# Power_Managment.net
KiCad netlist of a schematic drawn in Altium Designer
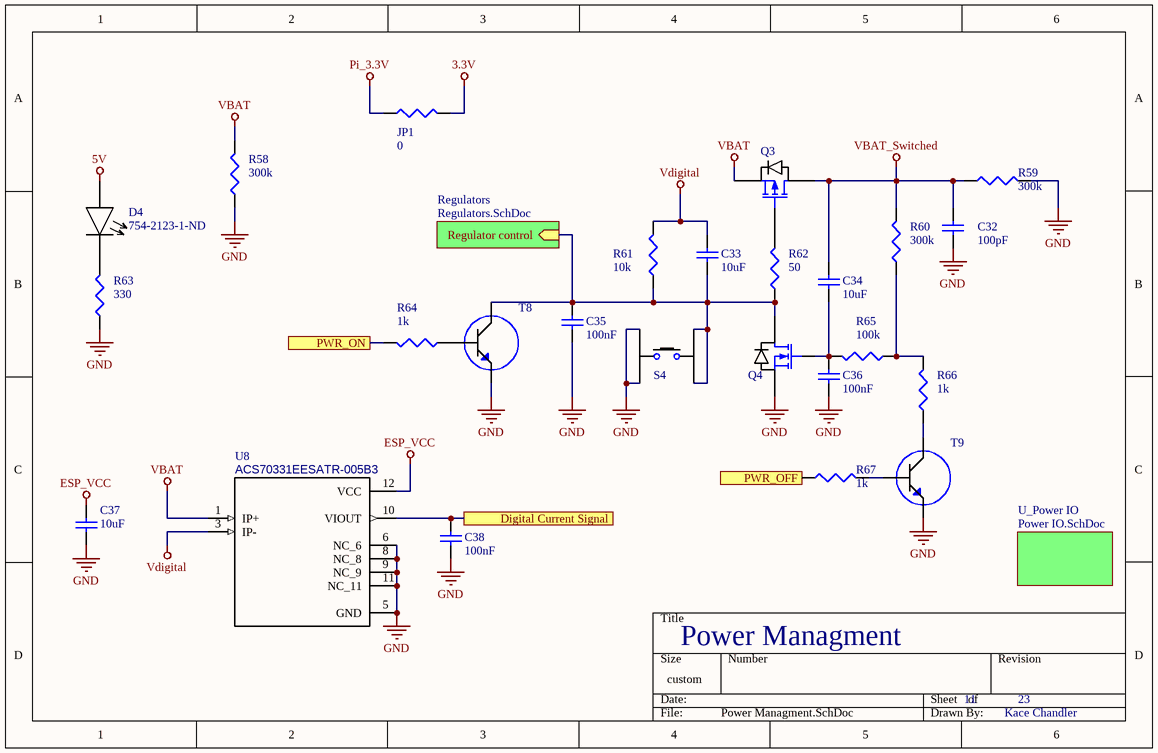
[diagram p0: Power Managment.SchDoc]

(export (version "E")
  (design (tool "Eeschema 10.0.6"))
  (components
    (comp (ref "C32")
      (value "100pF")
      (footprint "Electrolytic Cap")
      (description "Capacitor")
      (fields (field (name "Comment") "Cap") (field (name "PUBLISHER") "Altium Limited"))
      (libsource (lib "Miscellaneous Devices") (part "Cap"))
    )
    (comp (ref "C33")
      (value "10uF")
      (footprint "0603 to 0805 SMD")
      (description "Capacitor")
      (fields (field (name "Comment") "Cap") (field (name "PUBLISHER") "Altium Limited"))
      (libsource (lib "Miscellaneous Devices") (part "Cap"))
    )
    (comp (ref "C34")
      (value "10uF")
      (footprint "0603 to 0805 SMD")
      (description "Capacitor")
      (fields (field (name "Comment") "Cap") (field (name "PUBLISHER") "Altium Limited"))
      (libsource (lib "Miscellaneous Devices") (part "Cap"))
    )
    (comp (ref "C35")
      (value "100nF")
      (footprint "0603 to 0805 SMD")
      (description "Capacitor")
      (fields (field (name "Comment") "Cap") (field (name "PUBLISHER") "Altium Limited"))
      (libsource (lib "Miscellaneous Devices") (part "Cap"))
    )
    (comp (ref "C36")
      (value "100nF")
      (footprint "0603 to 0805 SMD")
      (description "Capacitor")
      (fields (field (name "Comment") "Cap") (field (name "PUBLISHER") "Altium Limited"))
      (libsource (lib "Miscellaneous Devices") (part "Cap"))
    )
    (comp (ref "C37")
      (value "10uF")
      (footprint "0805 Footprint")
      (description "Capacitor")
      (fields (field (name "Comment") "Cap") (field (name "PUBLISHER") "Altium Limited"))
      (libsource (lib "Miscellaneous Devices") (part "Cap"))
    )
    (comp (ref "C38")
      (value "100nF")
      (footprint "0805 Footprint")
      (description "Capacitor")
      (fields (field (name "Comment") "Cap") (field (name "PUBLISHER") "Altium Limited"))
      (libsource (lib "Miscellaneous Devices") (part "Cap"))
    )
    (comp (ref "D4")
      (value "LED_R")
      (footprint "0402 footprint")
      (fields (field (name "SUPPLIER PART NUMBER 1") "754-2123-1-ND"))
      (libsource (lib "AvionicsParts") (part "LED_R"))
    )
    (comp (ref "JP1")
      (value "0")
      (footprint "0603 TO 1210 SMD")
      (description "Resistor")
      (fields (field (name "Comment") "Res3") (field (name "PUBLISHER") "Altium Limited"))
      (libsource (lib "Miscellaneous Devices") (part "Res3"))
    )
    (comp (ref "Q3")
      (value "P-Channel")
      (footprint "P Channel MOSFET")
      (libsource (lib "AvionicsParts") (part "P-Channel"))
    )
    (comp (ref "Q4")
      (value "N-Channel")
      (footprint "N Channel MOSFET")
      (libsource (lib "AvionicsParts") (part "N-Channel"))
    )
    (comp (ref "R58")
      (value "300k")
      (footprint "0603 Footprint")
      (description "Resistor")
      (fields (field (name "Comment") "Res3") (field (name "PUBLISHER") "Altium Limited"))
      (libsource (lib "Miscellaneous Devices") (part "Res3"))
    )
    (comp (ref "R59")
      (value "300k")
      (footprint "0603 Footprint")
      (description "Resistor")
      (fields (field (name "Comment") "Res3") (field (name "PUBLISHER") "Altium Limited"))
      (libsource (lib "Miscellaneous Devices") (part "Res3"))
    )
    (comp (ref "R60")
      (value "300k")
      (footprint "0603 Footprint")
      (description "Resistor")
      (fields (field (name "Comment") "Res3") (field (name "PUBLISHER") "Altium Limited"))
      (libsource (lib "Miscellaneous Devices") (part "Res3"))
    )
    (comp (ref "R61")
      (value "10k")
      (footprint "0603 Footprint")
      (description "Resistor")
      (fields (field (name "Comment") "Res3") (field (name "PUBLISHER") "Altium Limited"))
      (libsource (lib "Miscellaneous Devices") (part "Res3"))
    )
    (comp (ref "R62")
      (value "50")
      (footprint "0603 Footprint")
      (description "Resistor")
      (fields (field (name "Comment") "Res3") (field (name "PUBLISHER") "Altium Limited"))
      (libsource (lib "Miscellaneous Devices") (part "Res3"))
    )
    (comp (ref "R63")
      (value "330")
      (footprint "0603 Footprint")
      (description "Resistor")
      (fields (field (name "Comment") "Res3") (field (name "PUBLISHER") "Altium Limited"))
      (libsource (lib "Miscellaneous Devices") (part "Res3"))
    )
    (comp (ref "R64")
      (value "1k")
      (footprint "0603 Footprint")
      (description "Resistor")
      (fields (field (name "Comment") "Res3") (field (name "PUBLISHER") "Altium Limited"))
      (libsource (lib "Miscellaneous Devices") (part "Res3"))
    )
    (comp (ref "R65")
      (value "100k")
      (footprint "0603 Footprint")
      (description "Resistor")
      (fields (field (name "Comment") "Res3") (field (name "PUBLISHER") "Altium Limited"))
      (libsource (lib "Miscellaneous Devices") (part "Res3"))
    )
    (comp (ref "R66")
      (value "1k")
      (footprint "0603 Footprint")
      (description "Resistor")
      (fields (field (name "Comment") "Res3") (field (name "PUBLISHER") "Altium Limited"))
      (libsource (lib "Miscellaneous Devices") (part "Res3"))
    )
    (comp (ref "R67")
      (value "1k")
      (footprint "0603 Footprint")
      (description "Resistor")
      (fields (field (name "Comment") "Res3") (field (name "PUBLISHER") "Altium Limited"))
      (libsource (lib "Miscellaneous Devices") (part "Res3"))
    )
    (comp (ref "S4")
      (value "434153017835")
      (footprint "*434153017835")
      (description "Switch Tactile Spst-No 0.05a 12v")
      (fields (field (name "MF") "Wurth Electronics"))
      (libsource (lib "AvionicsParts") (part "Pushbutton NO"))
    )
    (comp (ref "T8")
      (value "MMBT2222ALT1")
      (footprint "BJT")
      (description "Trans NPN 40V 0.6A SOT23")
      (fields (field (name "MF") "ON Semiconductor"))
      (libsource (lib "AvionicsParts") (part "BJT NPN"))
    )
    (comp (ref "T9")
      (value "MMBT2222ALT1")
      (footprint "BJT")
      (description "Trans NPN 40V 0.6A SOT23")
      (fields (field (name "MF") "ON Semiconductor"))
      (libsource (lib "AvionicsParts") (part "BJT NPN"))
    )
    (comp (ref "U8")
      (value "ACS70331EESATR-005B3")
      (footprint "*XDCR_ACS70331EESATR-005B3")
      (description "Current Sensor Current Sensor AC/DC Current 12-Pin QFN EP T/R")
      (fields (field (name "MF") "Allegro MicroSystems LLC") (field (name "MP") "ACS70331EESATR-005B3"))
      (libsource (lib "AvionicsParts") (part "2.5A Current Sensor"))
    )
  )
  (nets
    (net (code "1") (name "/Digital Current Signal") (class "Default")
      (node (ref "C38") (pin "2") (pinfunction "2_2") (pintype "passive"))
      (node (ref "U8") (pin "10") (pinfunction "VIOUT_10") (pintype "output"))
    )
    (net (code "2") (name "/PWR_OFF") (class "Default")
      (node (ref "R67") (pin "1") (pinfunction "1_1") (pintype "passive"))
    )
    (net (code "3") (name "/PWR_ON") (class "Default")
      (node (ref "R64") (pin "2") (pinfunction "2_2") (pintype "passive"))
    )
    (net (code "4") (name "/Regulator control") (class "Default")
      (node (ref "C33") (pin "1") (pinfunction "1_1") (pintype "passive"))
      (node (ref "C35") (pin "2") (pinfunction "2_2") (pintype "passive"))
      (node (ref "Q4") (pin "3") (pinfunction "D_3") (pintype "passive"))
      (node (ref "R61") (pin "1") (pinfunction "1_1") (pintype "passive"))
      (node (ref "R62") (pin "1") (pinfunction "1_1") (pintype "passive"))
      (node (ref "S4") (pin "1") (pinfunction "1_1") (pintype "passive"))
      (node (ref "S4") (pin "3") (pinfunction "2_3") (pintype "passive"))
      (node (ref "T8") (pin "3") (pinfunction "C_3") (pintype "passive"))
    )
    (net (code "5") (name "3.3V") (class "Default")
      (node (ref "JP1") (pin "2") (pinfunction "2_2") (pintype "passive"))
    )
    (net (code "6") (name "5V") (class "Default")
      (node (ref "D4") (pin "1") (pinfunction "1_1") (pintype "passive"))
    )
    (net (code "7") (name "ESP_VCC") (class "Default")
      (node (ref "C37") (pin "2") (pinfunction "2_2") (pintype "passive"))
      (node (ref "U8") (pin "12") (pinfunction "VCC_12") (pintype "power_in"))
    )
    (net (code "8") (name "GND") (class "Default")
      (node (ref "C32") (pin "1") (pinfunction "1_1") (pintype "passive"))
      (node (ref "C35") (pin "1") (pinfunction "1_1") (pintype "passive"))
      (node (ref "C36") (pin "1") (pinfunction "1_1") (pintype "passive"))
      (node (ref "C37") (pin "1") (pinfunction "1_1") (pintype "passive"))
      (node (ref "C38") (pin "1") (pinfunction "1_1") (pintype "passive"))
      (node (ref "Q4") (pin "2") (pinfunction "S_2") (pintype "passive"))
      (node (ref "R58") (pin "1") (pinfunction "1_1") (pintype "passive"))
      (node (ref "R59") (pin "2") (pinfunction "2_2") (pintype "passive"))
      (node (ref "R63") (pin "1") (pinfunction "1_1") (pintype "passive"))
      (node (ref "S4") (pin "2") (pinfunction "3_2") (pintype "passive"))
      (node (ref "S4") (pin "4") (pinfunction "4_4") (pintype "passive"))
      (node (ref "T8") (pin "2") (pinfunction "E_2") (pintype "passive"))
      (node (ref "T9") (pin "2") (pinfunction "E_2") (pintype "passive"))
      (node (ref "U8") (pin "11") (pinfunction "NC_11_11") (pintype "passive"))
      (node (ref "U8") (pin "5") (pinfunction "GND_5") (pintype "power_in"))
      (node (ref "U8") (pin "6") (pinfunction "NC_6_6") (pintype "passive"))
      (node (ref "U8") (pin "8") (pinfunction "NC_8_8") (pintype "passive"))
      (node (ref "U8") (pin "9") (pinfunction "NC_9_9") (pintype "passive"))
    )
    (net (code "9") (name "Net-(D4-Pad2)") (class "Default")
      (node (ref "D4") (pin "2") (pinfunction "2_2") (pintype "passive"))
      (node (ref "R63") (pin "2") (pinfunction "2_2") (pintype "passive"))
    )
    (net (code "10") (name "Net-(Q3-G)") (class "Default")
      (node (ref "Q3") (pin "1") (pinfunction "G_1") (pintype "passive"))
      (node (ref "R62") (pin "2") (pinfunction "2_2") (pintype "passive"))
    )
    (net (code "11") (name "Net-(Q4-G)") (class "Default")
      (node (ref "C34") (pin "1") (pinfunction "1_1") (pintype "passive"))
      (node (ref "C36") (pin "2") (pinfunction "2_2") (pintype "passive"))
      (node (ref "Q4") (pin "1") (pinfunction "G_1") (pintype "passive"))
      (node (ref "R65") (pin "2") (pinfunction "2_2") (pintype "passive"))
    )
    (net (code "12") (name "Net-(R60-Pad1)") (class "Default")
      (node (ref "R60") (pin "1") (pinfunction "1_1") (pintype "passive"))
      (node (ref "R65") (pin "1") (pinfunction "1_1") (pintype "passive"))
      (node (ref "R66") (pin "2") (pinfunction "2_2") (pintype "passive"))
    )
    (net (code "13") (name "Net-(T8-B)") (class "Default")
      (node (ref "R64") (pin "1") (pinfunction "1_1") (pintype "passive"))
      (node (ref "T8") (pin "1") (pinfunction "B_1") (pintype "passive"))
    )
    (net (code "14") (name "Net-(T9-B)") (class "Default")
      (node (ref "R67") (pin "2") (pinfunction "2_2") (pintype "passive"))
      (node (ref "T9") (pin "1") (pinfunction "B_1") (pintype "passive"))
    )
    (net (code "15") (name "Net-(T9-C)") (class "Default")
      (node (ref "R66") (pin "1") (pinfunction "1_1") (pintype "passive"))
      (node (ref "T9") (pin "3") (pinfunction "C_3") (pintype "passive"))
    )
    (net (code "16") (name "Pi_3.3V") (class "Default")
      (node (ref "JP1") (pin "1") (pinfunction "1_1") (pintype "passive"))
    )
    (net (code "17") (name "VBAT") (class "Default")
      (node (ref "Q3") (pin "2") (pinfunction "S_2") (pintype "passive"))
      (node (ref "R58") (pin "2") (pinfunction "2_2") (pintype "passive"))
      (node (ref "U8") (pin "1") (pinfunction "IP+_1") (pintype "input"))
    )
    (net (code "18") (name "VBAT_Switched") (class "Default")
      (node (ref "C32") (pin "2") (pinfunction "2_2") (pintype "passive"))
      (node (ref "C34") (pin "2") (pinfunction "2_2") (pintype "passive"))
      (node (ref "Q3") (pin "3") (pinfunction "D_3") (pintype "passive"))
      (node (ref "R59") (pin "1") (pinfunction "1_1") (pintype "passive"))
      (node (ref "R60") (pin "2") (pinfunction "2_2") (pintype "passive"))
    )
    (net (code "19") (name "Vdigital") (class "Default")
      (node (ref "C33") (pin "2") (pinfunction "2_2") (pintype "passive"))
      (node (ref "R61") (pin "2") (pinfunction "2_2") (pintype "passive"))
      (node (ref "U8") (pin "3") (pinfunction "IP-_3") (pintype "input"))
    )
  )
)
